# CAN_MAX3051_NB2IND02.net
KiCad netlist of a schematic drawn in Altium Designer
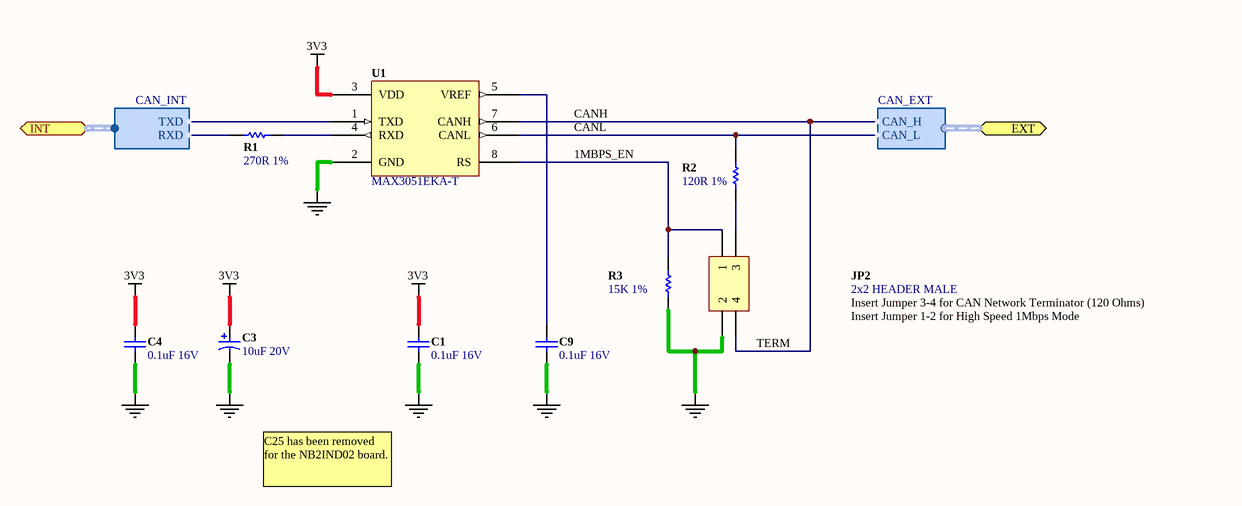
[diagram p0: CAN_MAX3051_NB2IND02.SchDoc]

(export (version "E")
  (design (tool "Eeschema 10.0.6"))
  (components
    (comp (ref "C1")
      (value "0.1uF 16V")
      (footprint "CAPC1005-STAR")
      (description "Capacitor, Ceramic, 0.1uF 10% 16V 0402 (1005) X7R")
      (fields (field (name "TOLERANCE") "10 %"))
      (libsource (lib "altium-import") (part "root_0_CAP-NP_"))
    )
    (comp (ref "C3")
      (value "10uF 20V")
      (footprint "CAPC3528-STAR")
      (description "Capacitor, Tantalum, 10uF 10% 20V MCCT-B (3528)")
      (fields (field (name "TOLERANCE") "10 %"))
      (libsource (lib "altium-import") (part "root_0_CAP-P_"))
    )
    (comp (ref "C4")
      (value "0.1uF 16V")
      (footprint "CAPC1005-STAR")
      (description "Capacitor, Ceramic, 0.1uF 10% 16V 0402 (1005) X7R")
      (fields (field (name "TOLERANCE") "10 %"))
      (libsource (lib "altium-import") (part "root_0_CAP-NP_"))
    )
    (comp (ref "C9")
      (value "0.1uF 16V")
      (footprint "CAPC1005-STAR")
      (description "Capacitor, Ceramic, 0.1uF 10% 16V 0402 (1005) X7R")
      (fields (field (name "TOLERANCE") "10 %"))
      (libsource (lib "altium-import") (part "root_0_CAP-NP_"))
    )
    (comp (ref "JP2")
      (value "2x2 HEADER MALE")
      (footprint "HDR2X2")
      (description "Header IDC, 2 x 2 Pin Vertical 2.54mm Pitch (Non-Boxed, Male)")
      (libsource (lib "AltiumDesignLibrary") (part "CON-HDR-2x2-STR"))
    )
    (comp (ref "R1")
      (value "270R 1%")
      (footprint "RESC1005-STAR")
      (description "Resistor, 270R 1% 0402 (1005)")
      (fields (field (name "TOLERANCE") "1 %"))
      (libsource (lib "altium-import") (part "root_1_RES_"))
    )
    (comp (ref "R2")
      (value "120R 1%")
      (footprint "RESC1005-STAR")
      (description "Resistor, 120R 1% 0402 (1005)")
      (fields (field (name "TOLERANCE") "1 %"))
      (libsource (lib "altium-import") (part "root_2_RES_"))
    )
    (comp (ref "R3")
      (value "15K 1%")
      (footprint "RESC1005-STAR")
      (description "Resistor, 15K 1% 0402 (1005)")
      (fields (field (name "TOLERANCE") "1 %"))
      (libsource (lib "altium-import") (part "root_2_RES_"))
    )
    (comp (ref "U1")
      (value "MAX3051EKA-T")
      (footprint "SOT65P280-8")
      (description "MAX3051EKA-T High-Speed CAN Transceiver SOT23-8")
      (libsource (lib "altium-import") (part "root_0_MCP2551_"))
    )
  )
  (nets
    (net (code "3") (name "/1MBPS_EN") (class "Default")
      (node (ref "JP2") (pin "1") (pinfunction "1_1") (pintype "passive"))
      (node (ref "R3") (pin "2") (pinfunction "2_2") (pintype "passive"))
      (node (ref "U1") (pin "8") (pinfunction "RS_8") (pintype "passive"))
    )
    (net (code "4") (name "/CANH") (class "Default")
      (node (ref "JP2") (pin "4") (pinfunction "4_4") (pintype "passive"))
      (node (ref "U1") (pin "7") (pinfunction "CANH_7") (pintype "output"))
    )
    (net (code "5") (name "/CANL") (class "Default")
      (node (ref "R2") (pin "2") (pinfunction "2_2") (pintype "passive"))
      (node (ref "U1") (pin "6") (pinfunction "CANL_6") (pintype "output"))
    )
    (net (code "6") (name "/RXD") (class "Default")
      (node (ref "R1") (pin "1") (pinfunction "1_1") (pintype "passive"))
    )
    (net (code "7") (name "/TXD") (class "Default")
      (node (ref "U1") (pin "1") (pinfunction "TXD_1") (pintype "input"))
    )
    (net (code "10") (name "3V3") (class "Default")
      (node (ref "C1") (pin "1") (pinfunction "1_1") (pintype "passive"))
      (node (ref "C3") (pin "1") (pinfunction "1_1") (pintype "passive"))
      (node (ref "C4") (pin "1") (pinfunction "1_1") (pintype "passive"))
      (node (ref "U1") (pin "3") (pinfunction "VDD_3") (pintype "power_in"))
    )
    (net (code "11") (name "GND") (class "Default")
      (node (ref "C1") (pin "2") (pinfunction "2_2") (pintype "passive"))
      (node (ref "C3") (pin "2") (pinfunction "2_2") (pintype "passive"))
      (node (ref "C4") (pin "2") (pinfunction "2_2") (pintype "passive"))
      (node (ref "C9") (pin "2") (pinfunction "2_2") (pintype "passive"))
      (node (ref "JP2") (pin "2") (pinfunction "2_2") (pintype "passive"))
      (node (ref "R3") (pin "1") (pinfunction "1_1") (pintype "passive"))
      (node (ref "U1") (pin "2") (pinfunction "GND_2") (pintype "power_in"))
    )
    (net (code "12") (name "Net-(JP2-Pad3)") (class "Default")
      (node (ref "JP2") (pin "3") (pinfunction "3_3") (pintype "passive"))
      (node (ref "R2") (pin "1") (pinfunction "1_1") (pintype "passive"))
    )
    (net (code "13") (name "Net-(U1-RXD)") (class "Default")
      (node (ref "R1") (pin "2") (pinfunction "2_2") (pintype "passive"))
      (node (ref "U1") (pin "4") (pinfunction "RXD_4") (pintype "output"))
    )
    (net (code "14") (name "Net-(U1-VREF)") (class "Default")
      (node (ref "C9") (pin "1") (pinfunction "1_1") (pintype "passive"))
      (node (ref "U1") (pin "5") (pinfunction "VREF_5") (pintype "output"))
    )
  )
)
